# Sheet4.net
KiCad netlist of a schematic drawn in Altium Designer
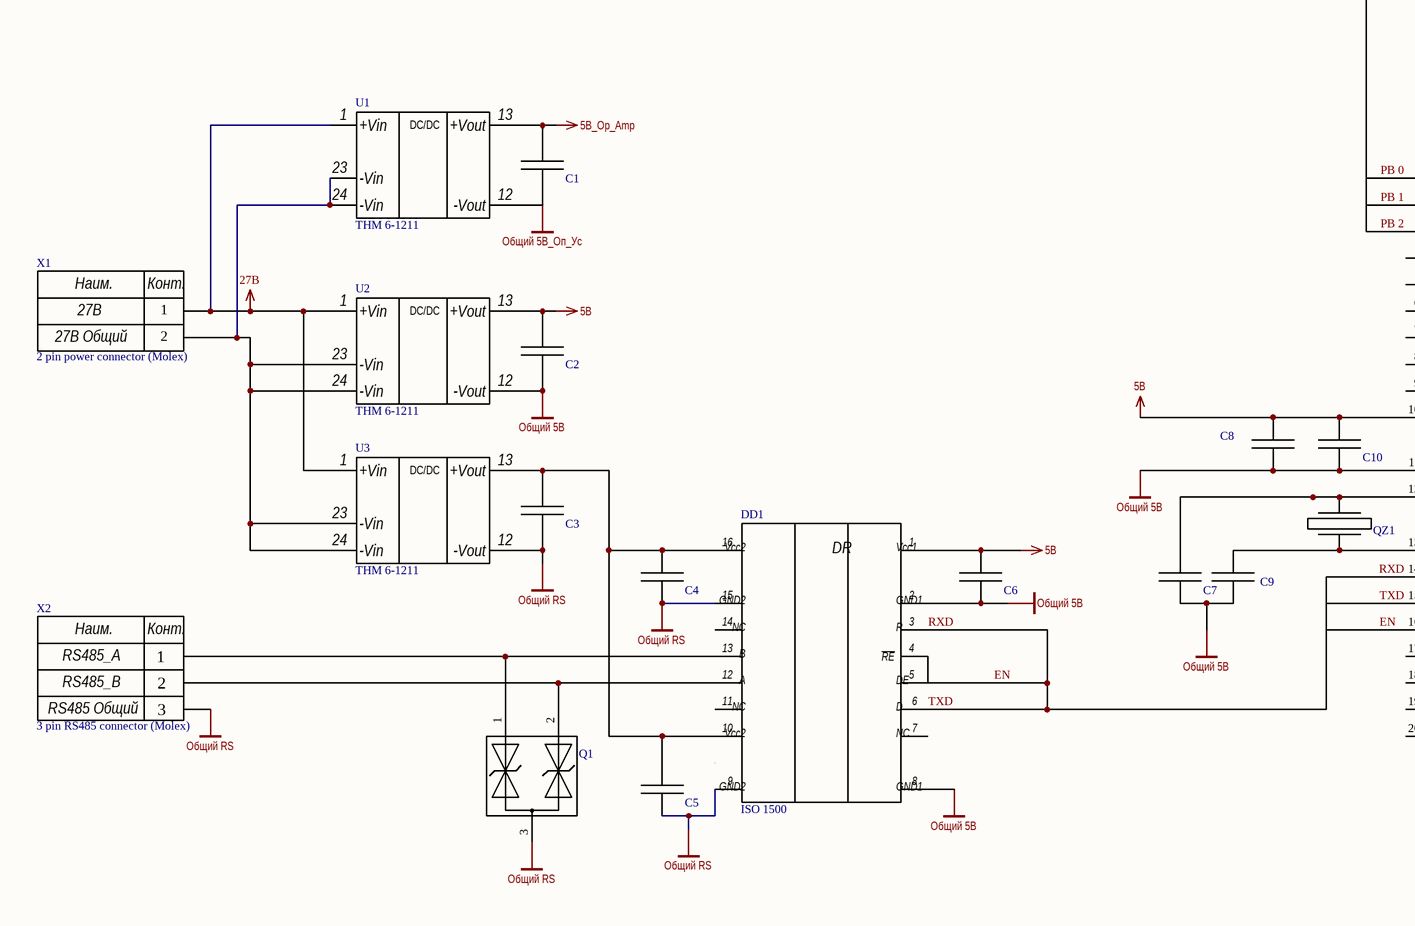
[diagram p0: Sheet4.SchDoc, left]
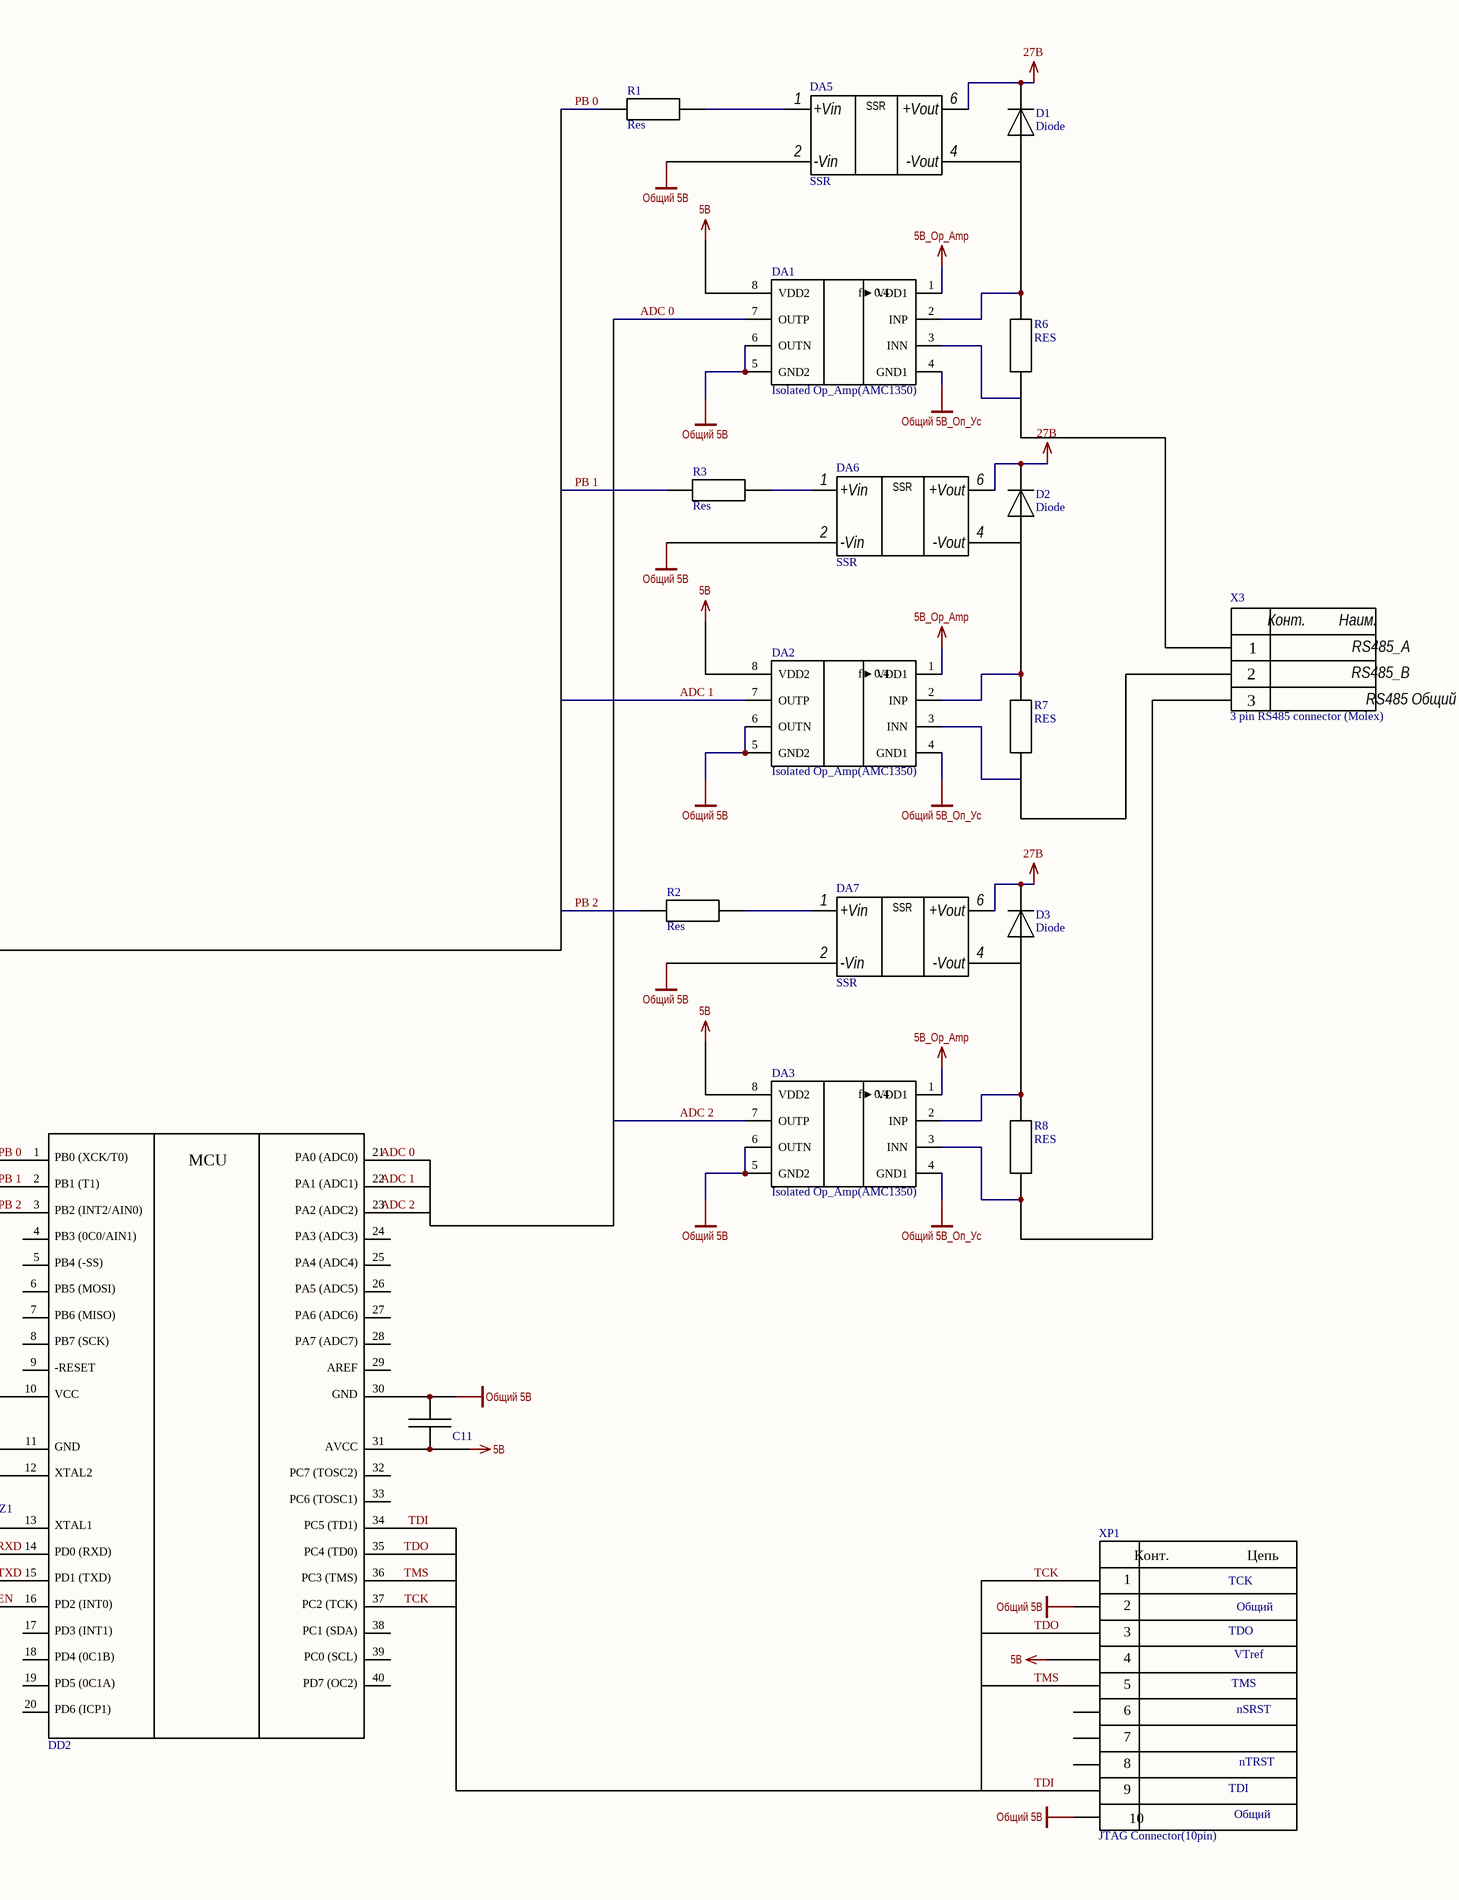
[diagram p1: Sheet4.SchDoc, right]

(export (version "E")
  (design (tool "Eeschema 10.0.6"))
  (components
    (comp (ref "C1") (value "CAP") (footprint "0805") (libsource (lib "Kursovoi proekt") (part "CAP")))
    (comp (ref "C2") (value "CAP") (footprint "0805") (libsource (lib "Kursovoi proekt") (part "CAP")))
    (comp (ref "C3") (value "CAP") (footprint "0805") (libsource (lib "Kursovoi proekt") (part "CAP")))
    (comp (ref "C4") (value "CAP") (footprint "0805") (libsource (lib "Kursovoi proekt") (part "CAP")))
    (comp (ref "C5") (value "CAP") (footprint "0805") (libsource (lib "Kursovoi proekt") (part "CAP")))
    (comp (ref "C6") (value "CAP") (footprint "0805") (libsource (lib "Kursovoi proekt") (part "CAP")))
    (comp (ref "C7") (value "CAP") (footprint "0805") (libsource (lib "Kursovoi proekt") (part "CAP")))
    (comp (ref "C8") (value "CAP") (footprint "0805") (libsource (lib "Kursovoi proekt") (part "CAP")))
    (comp (ref "C9") (value "CAP") (footprint "0805") (libsource (lib "Kursovoi proekt") (part "CAP")))
    (comp (ref "C10") (value "CAP") (footprint "0805") (libsource (lib "Kursovoi proekt") (part "CAP")))
    (comp (ref "C11") (value "CAP") (footprint "0805") (libsource (lib "Kursovoi proekt") (part "CAP")))
    (comp (ref "D1") (value "Diode") (footprint "Diode") (libsource (lib "Kursovoi proekt") (part "Diode")))
    (comp (ref "D2") (value "Diode") (footprint "Diode") (libsource (lib "Kursovoi proekt") (part "Diode")))
    (comp (ref "D3") (value "Diode") (footprint "Diode") (libsource (lib "Kursovoi proekt") (part "Diode")))
    (comp (ref "DA1")
      (value "Isolated Op_Amp(AMC1350)")
      (footprint "SOIC-8")
      (libsource (lib "Kursovoi proekt") (part "Isolated Op_Amp(AMC1350)"))
    )
    (comp (ref "DA2")
      (value "Isolated Op_Amp(AMC1350)")
      (footprint "SOIC-8")
      (libsource (lib "Kursovoi proekt") (part "Isolated Op_Amp(AMC1350)"))
    )
    (comp (ref "DA3")
      (value "Isolated Op_Amp(AMC1350)")
      (footprint "SOIC-8")
      (libsource (lib "Kursovoi proekt") (part "Isolated Op_Amp(AMC1350)"))
    )
    (comp (ref "DA5") (value "SSR") (footprint "DIP6") (libsource (lib "Kursovoi proekt") (part "SSR")))
    (comp (ref "DA6") (value "SSR") (footprint "DIP6") (libsource (lib "Kursovoi proekt") (part "SSR")))
    (comp (ref "DA7") (value "SSR") (footprint "DIP6") (libsource (lib "Kursovoi proekt") (part "SSR")))
    (comp (ref "DD1")
      (value "ISO 1500")
      (footprint "SSOP-16")
      (libsource (lib "Kursovoi proekt") (part "MAX 485"))
    )
    (comp (ref "DD2")
      (value "Atmega16")
      (footprint "TQFP-44")
      (libsource (lib "Kursovoi proekt") (part "Atmega16"))
    )
    (comp (ref "Q1")
      (value "Bipolar TVS diode")
      (footprint "SOT-23-3")
      (libsource (lib "Kursovoi proekt") (part "Bipolar TVS"))
    )
    (comp (ref "QZ1") (value "Quartz rez") (footprint "XTAL") (libsource (lib "Kursovoi proekt") (part "QZ")))
    (comp (ref "R1") (value "Res") (footprint "0805") (libsource (lib "Kursovoi proekt") (part "Res")))
    (comp (ref "R2") (value "Res") (footprint "0805") (libsource (lib "Kursovoi proekt") (part "Res")))
    (comp (ref "R3") (value "Res") (footprint "0805") (libsource (lib "Kursovoi proekt") (part "Res")))
    (comp (ref "R6") (value "RES") (footprint "0805") (libsource (lib "") (part "Res_1")))
    (comp (ref "R7") (value "RES") (footprint "0805") (libsource (lib "") (part "Res_1")))
    (comp (ref "R8") (value "RES") (footprint "0805") (libsource (lib "") (part "Res_1")))
    (comp (ref "U1")
      (value "THM 6-1211")
      (footprint "CONV_THM_10-2411")
      (description "6W 18-36Vin 5Vout")
      (libsource (lib "Kursovoi proekt") (part "THM 6-1211"))
    )
    (comp (ref "U2")
      (value "THM 6-1211")
      (footprint "CONV_THM_10-2411")
      (description "6W 18-36Vin 5Vout")
      (libsource (lib "Kursovoi proekt") (part "THM 6-1211"))
    )
    (comp (ref "U3")
      (value "THM 6-1211")
      (footprint "CONV_THM_10-2411")
      (description "3W 18-36Vin 5Vout")
      (libsource (lib "Kursovoi proekt") (part "THM 3-2411"))
    )
    (comp (ref "X1")
      (value "2 pin power connector (Molex)")
      (footprint "MolexMicroFit 2x1")
      (libsource (lib "Kursovoi proekt") (part "2 pin power connector (Molex)"))
    )
    (comp (ref "X2")
      (value "3 pin RS485 connector (Molex)")
      (footprint "MolexMicroFit 3x1")
      (libsource (lib "") (part "3 pin RS485 connector (Molex)_1"))
    )
    (comp (ref "X3")
      (value "3 pin RS485 connector (Molex)")
      (footprint "MolexMicroFit 3x1")
      (libsource (lib "Kursovoi proekt") (part "3 pin RS485 connector (Molex)"))
    )
    (comp (ref "XP1")
      (value "JTAG Connector(10pin)")
      (footprint "PLD 10")
      (libsource (lib "Kursovoi proekt") (part "JTAG Connector(10pin)"))
    )
  )
  (nets
    (net (code "1") (name "/ADC 0") (class "Default")
      (node (ref "DA1") (pin "7") (pinfunction "OUTP_7") (pintype "passive"))
      (node (ref "DD2") (pin "21") (pinfunction "21_21") (pintype "passive"))
    )
    (net (code "2") (name "/ADC 1") (class "Default")
      (node (ref "DA2") (pin "7") (pinfunction "OUTP_7") (pintype "passive"))
      (node (ref "DD2") (pin "22") (pinfunction "22_22") (pintype "passive"))
    )
    (net (code "3") (name "/ADC 2") (class "Default")
      (node (ref "DA3") (pin "7") (pinfunction "OUTP_7") (pintype "passive"))
      (node (ref "DD2") (pin "23") (pinfunction "23_23") (pintype "passive"))
    )
    (net (code "4") (name "/EN") (class "Default")
      (node (ref "DD1") (pin "3") (pinfunction "3_3") (pintype "passive"))
      (node (ref "DD1") (pin "4") (pinfunction "~{RE}_4") (pintype "passive"))
      (node (ref "DD1") (pin "5") (pinfunction "5_5") (pintype "passive"))
      (node (ref "DD1") (pin "6") (pinfunction "6_6") (pintype "passive"))
      (node (ref "DD2") (pin "14") (pinfunction "14_14") (pintype "passive"))
      (node (ref "DD2") (pin "15") (pinfunction "15_15") (pintype "passive"))
      (node (ref "DD2") (pin "16") (pinfunction "16_16") (pintype "passive"))
    )
    (net (code "5") (name "/PB 0") (class "Default")
      (node (ref "DD2") (pin "1") (pinfunction "1_1") (pintype "passive"))
      (node (ref "R1") (pin "1") (pinfunction "1_1") (pintype "passive"))
    )
    (net (code "6") (name "/PB 1") (class "Default")
      (node (ref "DD2") (pin "2") (pinfunction "2_2") (pintype "passive"))
      (node (ref "R3") (pin "1") (pinfunction "1_1") (pintype "passive"))
    )
    (net (code "7") (name "/PB 2") (class "Default")
      (node (ref "DD2") (pin "3") (pinfunction "3_3") (pintype "passive"))
      (node (ref "R2") (pin "1") (pinfunction "1_1") (pintype "passive"))
    )
    (net (code "8") (name "/TCK") (class "Default")
      (node (ref "DD2") (pin "37") (pinfunction "37_37") (pintype "passive"))
      (node (ref "XP1") (pin "1") (pinfunction "1_1") (pintype "passive"))
    )
    (net (code "9") (name "/TDI") (class "Default")
      (node (ref "DD2") (pin "34") (pinfunction "34_34") (pintype "passive"))
      (node (ref "XP1") (pin "9") (pinfunction "9_9") (pintype "passive"))
    )
    (net (code "10") (name "/TDO") (class "Default")
      (node (ref "DD2") (pin "35") (pinfunction "35_35") (pintype "passive"))
      (node (ref "XP1") (pin "3") (pinfunction "3_3") (pintype "passive"))
    )
    (net (code "11") (name "/TMS") (class "Default")
      (node (ref "DD2") (pin "36") (pinfunction "36_36") (pintype "passive"))
      (node (ref "XP1") (pin "5") (pinfunction "5_5") (pintype "passive"))
    )
    (net (code "12") (name "5В") (class "Default")
      (node (ref "C10") (pin "1") (pinfunction "1_1") (pintype "passive"))
      (node (ref "C11") (pin "1") (pinfunction "1_1") (pintype "passive"))
      (node (ref "C2") (pin "2") (pinfunction "2_2") (pintype "passive"))
      (node (ref "C6") (pin "2") (pinfunction "2_2") (pintype "passive"))
      (node (ref "C9") (pin "2") (pinfunction "2_2") (pintype "passive"))
      (node (ref "DA1") (pin "8") (pinfunction "VDD2_8") (pintype "passive"))
      (node (ref "DA2") (pin "8") (pinfunction "VDD2_8") (pintype "passive"))
      (node (ref "DA3") (pin "8") (pinfunction "VDD2_8") (pintype "passive"))
      (node (ref "DD1") (pin "1") (pinfunction "1_1") (pintype "passive"))
      (node (ref "DD2") (pin "10") (pinfunction "10_10") (pintype "passive"))
      (node (ref "DD2") (pin "31") (pinfunction "31_31") (pintype "passive"))
      (node (ref "U2") (pin "13") (pinfunction "+Vout_13") (pintype "passive"))
      (node (ref "XP1") (pin "4") (pinfunction "4_4") (pintype "passive"))
    )
    (net (code "13") (name "5В_Op_Amp") (class "Default")
      (node (ref "C1") (pin "2") (pinfunction "2_2") (pintype "passive"))
      (node (ref "DA1") (pin "1") (pinfunction "VDD1_1") (pintype "passive"))
      (node (ref "DA2") (pin "1") (pinfunction "VDD1_1") (pintype "passive"))
      (node (ref "DA3") (pin "1") (pinfunction "VDD1_1") (pintype "passive"))
      (node (ref "U1") (pin "13") (pinfunction "+Vout_13") (pintype "passive"))
    )
    (net (code "14") (name "27В") (class "Default")
      (node (ref "D1") (pin "1") (pinfunction "3_1") (pintype "passive"))
      (node (ref "D2") (pin "1") (pinfunction "3_1") (pintype "passive"))
      (node (ref "D3") (pin "1") (pinfunction "3_1") (pintype "passive"))
      (node (ref "DA5") (pin "6") (pinfunction "+Vout_6") (pintype "passive"))
      (node (ref "DA6") (pin "6") (pinfunction "+Vout_6") (pintype "passive"))
      (node (ref "DA7") (pin "6") (pinfunction "+Vout_6") (pintype "passive"))
      (node (ref "U1") (pin "1") (pinfunction "+Vin_1") (pintype "passive"))
      (node (ref "U2") (pin "1") (pinfunction "+Vin_1") (pintype "passive"))
      (node (ref "U3") (pin "1") (pinfunction "+Vin_1") (pintype "passive"))
      (node (ref "X1") (pin "1") (pinfunction "1_1") (pintype "passive"))
    )
    (net (code "15") (name "Net-(C7-Pad1)") (class "Default")
      (node (ref "C7") (pin "1") (pinfunction "1_1") (pintype "passive"))
      (node (ref "DD2") (pin "12") (pinfunction "12_12") (pintype "passive"))
      (node (ref "QZ1") (pin "2") (pinfunction "2_2") (pintype "passive"))
    )
    (net (code "16") (name "Net-(C8-Pad1)") (class "Default")
      (node (ref "C8") (pin "1") (pinfunction "1_1") (pintype "passive"))
      (node (ref "DD2") (pin "13") (pinfunction "13_13") (pintype "passive"))
      (node (ref "QZ1") (pin "1") (pinfunction "1_1") (pintype "passive"))
    )
    (net (code "17") (name "Net-(D1-1)") (class "Default")
      (node (ref "D1") (pin "2") (pinfunction "1_2") (pintype "passive"))
      (node (ref "DA1") (pin "2") (pinfunction "INP_2") (pintype "passive"))
      (node (ref "DA5") (pin "4") (pinfunction "-Vout_4") (pintype "passive"))
      (node (ref "R6") (pin "2") (pinfunction "2_2") (pintype "passive"))
    )
    (net (code "18") (name "Net-(D2-1)") (class "Default")
      (node (ref "D2") (pin "2") (pinfunction "1_2") (pintype "passive"))
      (node (ref "DA2") (pin "2") (pinfunction "INP_2") (pintype "passive"))
      (node (ref "DA6") (pin "4") (pinfunction "-Vout_4") (pintype "passive"))
      (node (ref "R7") (pin "2") (pinfunction "2_2") (pintype "passive"))
    )
    (net (code "19") (name "Net-(D3-1)") (class "Default")
      (node (ref "D3") (pin "2") (pinfunction "1_2") (pintype "passive"))
      (node (ref "DA3") (pin "2") (pinfunction "INP_2") (pintype "passive"))
      (node (ref "DA7") (pin "4") (pinfunction "-Vout_4") (pintype "passive"))
      (node (ref "R8") (pin "2") (pinfunction "2_2") (pintype "passive"))
    )
    (net (code "20") (name "Net-(DA1-INN)") (class "Default")
      (node (ref "DA1") (pin "3") (pinfunction "INN_3") (pintype "passive"))
      (node (ref "R6") (pin "1") (pinfunction "1_1") (pintype "passive"))
      (node (ref "X3") (pin "1") (pinfunction "1_1") (pintype "passive"))
    )
    (net (code "21") (name "Net-(DA2-INN)") (class "Default")
      (node (ref "DA2") (pin "3") (pinfunction "INN_3") (pintype "passive"))
      (node (ref "R7") (pin "1") (pinfunction "1_1") (pintype "passive"))
      (node (ref "X3") (pin "2") (pinfunction "2_2") (pintype "passive"))
    )
    (net (code "22") (name "Net-(DA3-INN)") (class "Default")
      (node (ref "DA3") (pin "3") (pinfunction "INN_3") (pintype "passive"))
      (node (ref "R8") (pin "1") (pinfunction "1_1") (pintype "passive"))
      (node (ref "X3") (pin "3") (pinfunction "3_3") (pintype "passive"))
    )
    (net (code "23") (name "Net-(DA5-+Vin)") (class "Default")
      (node (ref "DA5") (pin "1") (pinfunction "+Vin_1") (pintype "passive"))
      (node (ref "R1") (pin "2") (pinfunction "2_2") (pintype "passive"))
    )
    (net (code "24") (name "Net-(DA6-+Vin)") (class "Default")
      (node (ref "DA6") (pin "1") (pinfunction "+Vin_1") (pintype "passive"))
      (node (ref "R3") (pin "2") (pinfunction "2_2") (pintype "passive"))
    )
    (net (code "25") (name "Net-(DA7-+Vin)") (class "Default")
      (node (ref "DA7") (pin "1") (pinfunction "+Vin_1") (pintype "passive"))
      (node (ref "R2") (pin "2") (pinfunction "2_2") (pintype "passive"))
    )
    (net (code "26") (name "Net-(DD1-Pad12)") (class "Default")
      (node (ref "DD1") (pin "12") (pinfunction "12_12") (pintype "passive"))
      (node (ref "Q1") (pin "2") (pinfunction "2_2") (pintype "passive"))
      (node (ref "X2") (pin "2") (pinfunction "2_2") (pintype "passive"))
    )
    (net (code "27") (name "Net-(DD1-Pad13)") (class "Default")
      (node (ref "DD1") (pin "13") (pinfunction "13_13") (pintype "passive"))
      (node (ref "Q1") (pin "1") (pinfunction "1_1") (pintype "passive"))
      (node (ref "X2") (pin "1") (pinfunction "1_1") (pintype "passive"))
    )
    (net (code "28") (name "Net-(U1--Vin-Pad23)") (class "Default")
      (node (ref "U1") (pin "23") (pinfunction "-Vin_23") (pintype "passive"))
      (node (ref "U1") (pin "24") (pinfunction "-Vin_24") (pintype "passive"))
      (node (ref "U2") (pin "23") (pinfunction "-Vin_23") (pintype "passive"))
      (node (ref "U2") (pin "24") (pinfunction "-Vin_24") (pintype "passive"))
      (node (ref "U3") (pin "23") (pinfunction "-Vin_23") (pintype "passive"))
      (node (ref "U3") (pin "24") (pinfunction "-Vin_24") (pintype "passive"))
      (node (ref "X1") (pin "2") (pinfunction "2_2") (pintype "passive"))
    )
    (net (code "29") (name "Net-(U3-+Vout)") (class "Default")
      (node (ref "C3") (pin "2") (pinfunction "2_2") (pintype "passive"))
      (node (ref "C4") (pin "2") (pinfunction "2_2") (pintype "passive"))
      (node (ref "C5") (pin "2") (pinfunction "2_2") (pintype "passive"))
      (node (ref "DD1") (pin "10") (pinfunction "10_10") (pintype "passive"))
      (node (ref "DD1") (pin "16") (pinfunction "16_16") (pintype "passive"))
      (node (ref "U3") (pin "13") (pinfunction "+Vout_13") (pintype "passive"))
    )
    (net (code "30") (name "unconnected-(DD1-Pad7)") (class "Default")
      (node (ref "DD1") (pin "7") (pinfunction "7_7") (pintype "passive"))
    )
    (net (code "31") (name "unconnected-(DD1-Pad11)") (class "Default")
      (node (ref "DD1") (pin "11") (pinfunction "11_11") (pintype "passive"))
    )
    (net (code "32") (name "unconnected-(DD1-Pad14)") (class "Default")
      (node (ref "DD1") (pin "14") (pinfunction "14_14") (pintype "passive"))
    )
    (net (code "33") (name "unconnected-(DD2-Pad4)") (class "Default")
      (node (ref "DD2") (pin "4") (pinfunction "4_4") (pintype "passive"))
    )
    (net (code "34") (name "unconnected-(DD2-Pad5)") (class "Default")
      (node (ref "DD2") (pin "5") (pinfunction "5_5") (pintype "passive"))
    )
    (net (code "35") (name "unconnected-(DD2-Pad6)") (class "Default")
      (node (ref "DD2") (pin "6") (pinfunction "6_6") (pintype "passive"))
    )
    (net (code "36") (name "unconnected-(DD2-Pad7)") (class "Default")
      (node (ref "DD2") (pin "7") (pinfunction "7_7") (pintype "passive"))
    )
    (net (code "37") (name "unconnected-(DD2-Pad8)") (class "Default")
      (node (ref "DD2") (pin "8") (pinfunction "8_8") (pintype "passive"))
    )
    (net (code "38") (name "unconnected-(DD2-Pad9)") (class "Default")
      (node (ref "DD2") (pin "9") (pinfunction "9_9") (pintype "passive"))
    )
    (net (code "39") (name "unconnected-(DD2-Pad17)") (class "Default")
      (node (ref "DD2") (pin "17") (pinfunction "17_17") (pintype "passive"))
    )
    (net (code "40") (name "unconnected-(DD2-Pad18)") (class "Default")
      (node (ref "DD2") (pin "18") (pinfunction "18_18") (pintype "passive"))
    )
    (net (code "41") (name "unconnected-(DD2-Pad19)") (class "Default")
      (node (ref "DD2") (pin "19") (pinfunction "19_19") (pintype "passive"))
    )
    (net (code "42") (name "unconnected-(DD2-Pad20)") (class "Default")
      (node (ref "DD2") (pin "20") (pinfunction "20_20") (pintype "passive"))
    )
    (net (code "43") (name "unconnected-(DD2-Pad24)") (class "Default")
      (node (ref "DD2") (pin "24") (pinfunction "24_24") (pintype "passive"))
    )
    (net (code "44") (name "unconnected-(DD2-Pad25)") (class "Default")
      (node (ref "DD2") (pin "25") (pinfunction "25_25") (pintype "passive"))
    )
    (net (code "45") (name "unconnected-(DD2-Pad26)") (class "Default")
      (node (ref "DD2") (pin "26") (pinfunction "26_26") (pintype "passive"))
    )
    (net (code "46") (name "unconnected-(DD2-Pad27)") (class "Default")
      (node (ref "DD2") (pin "27") (pinfunction "27_27") (pintype "passive"))
    )
    (net (code "47") (name "unconnected-(DD2-Pad28)") (class "Default")
      (node (ref "DD2") (pin "28") (pinfunction "28_28") (pintype "passive"))
    )
    (net (code "48") (name "unconnected-(DD2-Pad29)") (class "Default")
      (node (ref "DD2") (pin "29") (pinfunction "29_29") (pintype "passive"))
    )
    (net (code "49") (name "unconnected-(DD2-Pad32)") (class "Default")
      (node (ref "DD2") (pin "32") (pinfunction "32_32") (pintype "passive"))
    )
    (net (code "50") (name "unconnected-(DD2-Pad33)") (class "Default")
      (node (ref "DD2") (pin "33") (pinfunction "33_33") (pintype "passive"))
    )
    (net (code "51") (name "unconnected-(DD2-Pad38)") (class "Default")
      (node (ref "DD2") (pin "38") (pinfunction "38_38") (pintype "passive"))
    )
    (net (code "52") (name "unconnected-(DD2-Pad39)") (class "Default")
      (node (ref "DD2") (pin "39") (pinfunction "39_39") (pintype "passive"))
    )
    (net (code "53") (name "unconnected-(DD2-Pad40)") (class "Default")
      (node (ref "DD2") (pin "40") (pinfunction "40_40") (pintype "passive"))
    )
    (net (code "54") (name "unconnected-(XP1-Pad6)") (class "Default")
      (node (ref "XP1") (pin "6") (pinfunction "6_6") (pintype "passive"))
    )
    (net (code "55") (name "unconnected-(XP1-Pad7)") (class "Default")
      (node (ref "XP1") (pin "7") (pinfunction "7_7") (pintype "passive"))
    )
    (net (code "56") (name "unconnected-(XP1-Pad8)") (class "Default")
      (node (ref "XP1") (pin "8") (pinfunction "8_8") (pintype "passive"))
    )
    (net (code "57") (name "Общий 5В") (class "Default")
      (node (ref "C10") (pin "2") (pinfunction "2_2") (pintype "passive"))
      (node (ref "C11") (pin "2") (pinfunction "2_2") (pintype "passive"))
      (node (ref "C2") (pin "1") (pinfunction "1_1") (pintype "passive"))
      (node (ref "C6") (pin "1") (pinfunction "1_1") (pintype "passive"))
      (node (ref "C7") (pin "2") (pinfunction "2_2") (pintype "passive"))
      (node (ref "C8") (pin "2") (pinfunction "2_2") (pintype "passive"))
      (node (ref "C9") (pin "1") (pinfunction "1_1") (pintype "passive"))
      (node (ref "DA1") (pin "5") (pinfunction "GND2_5") (pintype "passive"))
      (node (ref "DA1") (pin "6") (pinfunction "OUTN_6") (pintype "passive"))
      (node (ref "DA2") (pin "5") (pinfunction "GND2_5") (pintype "passive"))
      (node (ref "DA2") (pin "6") (pinfunction "OUTN_6") (pintype "passive"))
      (node (ref "DA3") (pin "5") (pinfunction "GND2_5") (pintype "passive"))
      (node (ref "DA3") (pin "6") (pinfunction "OUTN_6") (pintype "passive"))
      (node (ref "DA5") (pin "2") (pinfunction "-Vin_2") (pintype "passive"))
      (node (ref "DA6") (pin "2") (pinfunction "-Vin_2") (pintype "passive"))
      (node (ref "DA7") (pin "2") (pinfunction "-Vin_2") (pintype "passive"))
      (node (ref "DD1") (pin "2") (pinfunction "2_2") (pintype "passive"))
      (node (ref "DD1") (pin "8") (pinfunction "8_8") (pintype "passive"))
      (node (ref "DD2") (pin "11") (pinfunction "11_11") (pintype "passive"))
      (node (ref "DD2") (pin "30") (pinfunction "30_30") (pintype "passive"))
      (node (ref "U2") (pin "12") (pinfunction "-Vout_12") (pintype "passive"))
      (node (ref "XP1") (pin "10") (pinfunction "10_10") (pintype "passive"))
      (node (ref "XP1") (pin "2") (pinfunction "2_2") (pintype "passive"))
    )
    (net (code "58") (name "Общий 5В_Оп_Ус") (class "Default")
      (node (ref "C1") (pin "1") (pinfunction "1_1") (pintype "passive"))
      (node (ref "DA1") (pin "4") (pinfunction "GND1_4") (pintype "passive"))
      (node (ref "DA2") (pin "4") (pinfunction "GND1_4") (pintype "passive"))
      (node (ref "DA3") (pin "4") (pinfunction "GND1_4") (pintype "passive"))
      (node (ref "U1") (pin "12") (pinfunction "-Vout_12") (pintype "passive"))
    )
    (net (code "59") (name "Общий RS") (class "Default")
      (node (ref "C3") (pin "1") (pinfunction "1_1") (pintype "passive"))
      (node (ref "C4") (pin "1") (pinfunction "1_1") (pintype "passive"))
      (node (ref "C5") (pin "1") (pinfunction "1_1") (pintype "passive"))
      (node (ref "DD1") (pin "15") (pinfunction "15_15") (pintype "passive"))
      (node (ref "DD1") (pin "9") (pinfunction "9_9") (pintype "passive"))
      (node (ref "Q1") (pin "3") (pinfunction "3_3") (pintype "passive"))
      (node (ref "U3") (pin "12") (pinfunction "-Vout_12") (pintype "passive"))
      (node (ref "X2") (pin "3") (pinfunction "3_3") (pintype "passive"))
    )
  )
)
